# Battery_Manager.net
KiCad netlist of a schematic drawn in Altium Designer
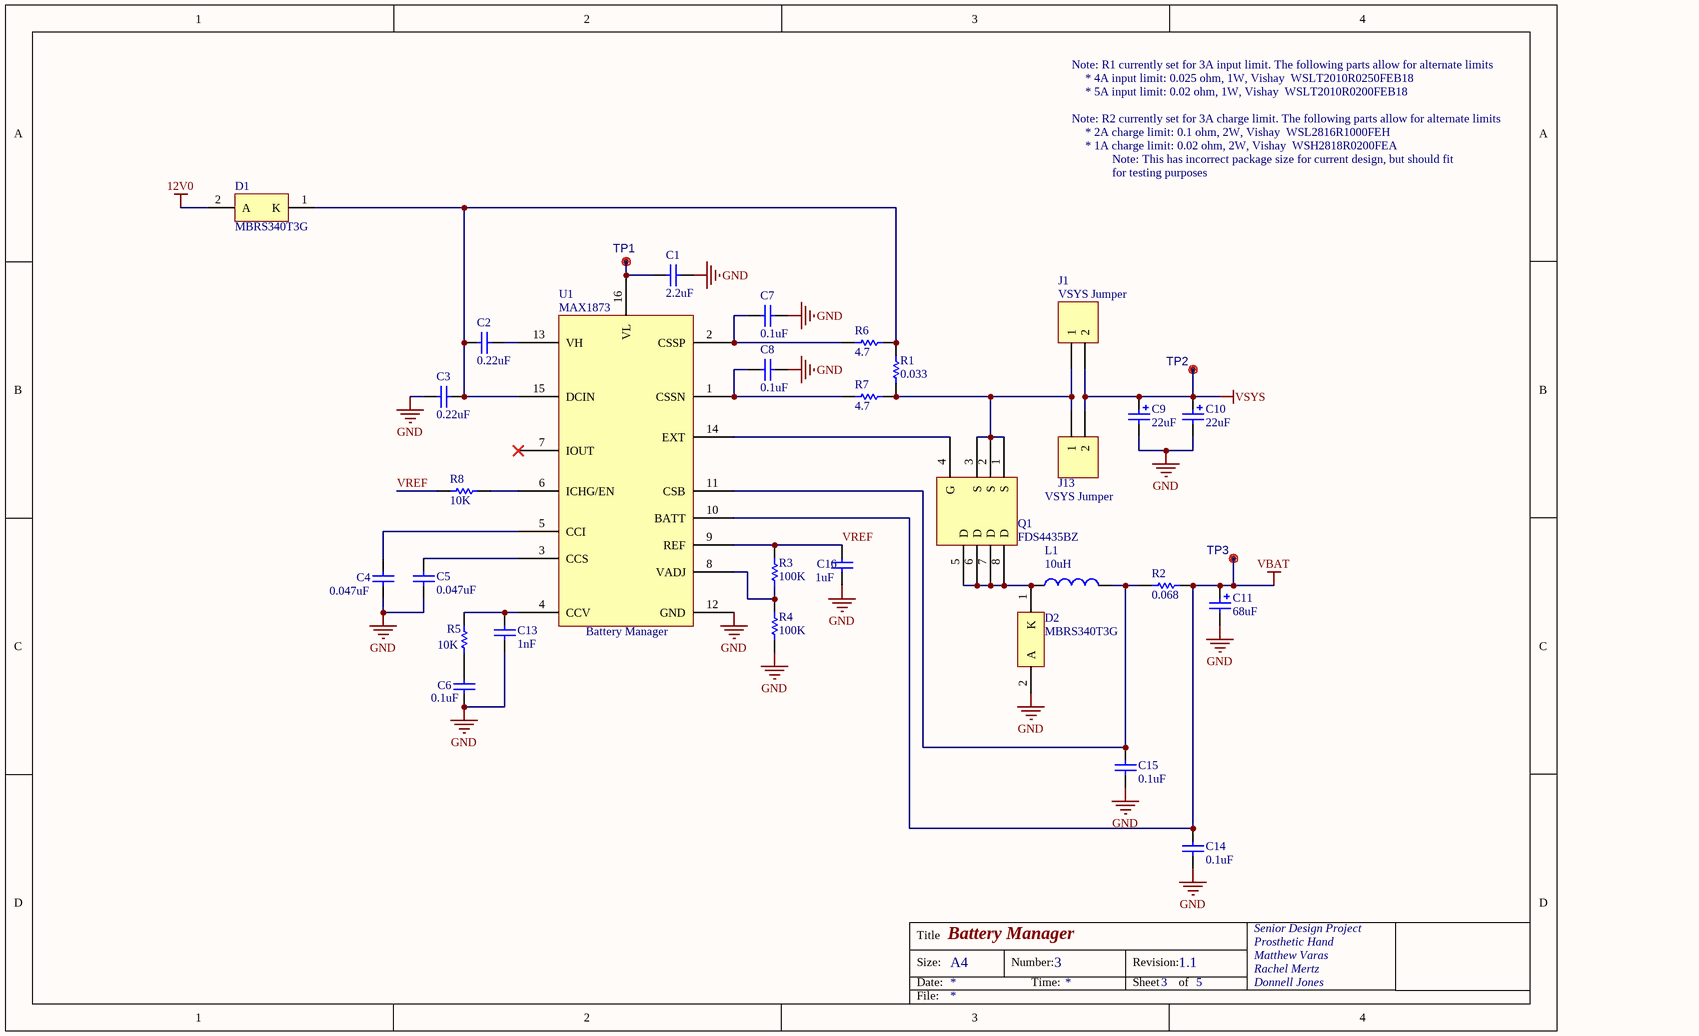
[diagram p0: Battery Manager.SchDoc]

(export (version "E")
  (design (tool "Eeschema 10.0.6"))
  (components
    (comp (ref "C1")
      (value "2.2uF")
      (footprint "CAPC0805(2012)145_N")
      (description "CAP CER 2.2UF 50V X5R 0805")
      (fields (field (name "TOLERANCE") "Â±10%"))
      (libsource (lib "Altium Content Vault") (part "CMP-1036-04844-1"))
    )
    (comp (ref "C2")
      (value "0.22uF")
      (footprint "CAPC0805(2012)145_N")
      (description "CAP CER 0.22UF 35V X5R 0805")
      (fields (field (name "TOLERANCE") "Â±10%"))
      (libsource (lib "Altium Content Vault") (part "CMP-1036-04552-1"))
    )
    (comp (ref "C3")
      (value "0.22uF")
      (footprint "CAPC0805(2012)145_N")
      (description "CAP CER 0.22UF 35V X5R 0805")
      (fields (field (name "TOLERANCE") "Â±10%"))
      (libsource (lib "Altium Content Vault") (part "CMP-1036-04552-1"))
    )
    (comp (ref "C4")
      (value "0.047uF")
      (footprint "CAPC0805(2012)75_N")
      (description "CAP CER 0.047UF 50V X7R 0805")
      (fields (field (name "TOLERANCE") "Â±10%"))
      (libsource (lib "Altium Content Vault") (part "CMP-1036-04259-1"))
    )
    (comp (ref "C5")
      (value "0.047uF")
      (footprint "CAPC0805(2012)75_N")
      (description "CAP CER 0.047UF 50V X7R 0805")
      (fields (field (name "TOLERANCE") "Â±10%"))
      (libsource (lib "Altium Content Vault") (part "CMP-1036-04259-1"))
    )
    (comp (ref "C6")
      (value "0.1uF")
      (footprint "CAPC0805(2012)145_N")
      (description "CAP CER 0.1UF 50V X7R 0805")
      (fields (field (name "TOLERANCE") "Â±10%"))
      (libsource (lib "Altium Content Vault") (part "CMP-1036-04419-1"))
    )
    (comp (ref "C7")
      (value "0.1uF")
      (footprint "CAPC0805(2012)145_N")
      (description "CAP CER 0.1UF 50V X7R 0805")
      (fields (field (name "TOLERANCE") "Â±10%"))
      (libsource (lib "Altium Content Vault") (part "CMP-1036-04419-1"))
    )
    (comp (ref "C8")
      (value "0.1uF")
      (footprint "CAPC0805(2012)145_N")
      (description "CAP CER 0.1UF 50V X7R 0805")
      (fields (field (name "TOLERANCE") "Â±10%"))
      (libsource (lib "Altium Content Vault") (part "CMP-1036-04419-1"))
    )
    (comp (ref "C9")
      (value "22uF")
      (footprint "Cap Tant D")
      (description "CAP TANT 22UF 35V 10% 2917")
      (libsource (lib "Miscellaneous Devices") (part "Cap Pol2"))
    )
    (comp (ref "C10")
      (value "22uF")
      (footprint "Cap Tant D")
      (description "CAP TANT 22UF 35V 10% 2917")
      (libsource (lib "Miscellaneous Devices") (part "Cap Pol2"))
    )
    (comp (ref "C11")
      (value "68uF")
      (footprint "Cap Tant E")
      (description "CAP TANT 68UF 25V 20% 2917")
      (libsource (lib "Miscellaneous Devices") (part "Cap Pol2"))
    )
    (comp (ref "C13")
      (value "1nF")
      (footprint "CAPC0603(1608)100_N")
      (description "CAP CER 1000PF 50V X7R 0603")
      (fields (field (name "TOLERANCE") "Â±10%"))
      (libsource (lib "Altium Content Vault") (part "CMP-1035-01889-1"))
    )
    (comp (ref "C14")
      (value "0.1uF")
      (footprint "CAPC0805(2012)145_N")
      (description "CAP CER 0.1UF 50V X7R 0805")
      (fields (field (name "TOLERANCE") "Â±10%"))
      (libsource (lib "Altium Content Vault") (part "CMP-1036-04419-1"))
    )
    (comp (ref "C15")
      (value "0.1uF")
      (footprint "CAPC0805(2012)145_N")
      (description "CAP CER 0.1UF 50V X7R 0805")
      (fields (field (name "TOLERANCE") "Â±10%"))
      (libsource (lib "Altium Content Vault") (part "CMP-1036-04419-1"))
    )
    (comp (ref "C16")
      (value "1uF")
      (footprint "CAPC0805(2012)100_N")
      (description "CAP CER 1UF 25V X7R 0805")
      (fields (field (name "TOLERANCE") "Â±10%"))
      (libsource (lib "Altium Content Vault") (part "CMP-1036-04737-1"))
    )
    (comp (ref "D1")
      (value "MBRS340T3G")
      (footprint "ONSC-SMC-2-403-03_V")
      (description "DIODE SCHOTTKY 40V 4A SMC")
      (fields (field (name "MANUFACTURER") "On Semiconductor"))
      (libsource (lib "") (part "CMP-1055-00380-1_1"))
    )
    (comp (ref "D2")
      (value "MBRS340T3G")
      (footprint "ONSC-SMC-2-403-03_V")
      (description "DIODE SCHOTTKY 40V 4A SMC")
      (fields (field (name "MANUFACTURER") "On Semiconductor"))
      (libsource (lib "Altium Content Vault") (part "CMP-1055-00380-1"))
    )
    (comp (ref "J1")
      (value "VSYS Jumper")
      (footprint "HDR1X2")
      (description "CONN HEADER .100 SINGL STR 2POS")
      (fields (field (name "PUBLISHER") "Altium Limited"))
      (libsource (lib "Miscellaneous Connectors") (part "Header 2"))
    )
    (comp (ref "J13")
      (value "VSYS Jumper")
      (footprint "HDR1X2")
      (description "CONN HEADER .100 SINGL STR 2POS")
      (fields (field (name "PUBLISHER") "Altium Limited"))
      (libsource (lib "") (part "Header 2_1"))
    )
    (comp (ref "L1")
      (value "10uH")
      (footprint "SRR1260 Ind")
      (description "FIXED IND 10UH 5.5A 20 MOHM SMD")
      (libsource (lib "Prosthetic Hand Schematic Lib") (part "SRR1260A-100MCT-ND"))
    )
    (comp (ref "Q1")
      (value "FDS4435BZ")
      (footprint "SOIC-8")
      (description "MOSFET P-CH 30V 8.8A 8-SOIC")
      (libsource (lib "Prosthetic Hand Schematic Lib") (part "FDS4435BZ"))
    )
    (comp (ref "R1")
      (value "0.033")
      (footprint "RESC2010(5025)_N")
      (description "RES SMD 0.033 OHM 1% 1W 2010")
      (fields (field (name "TOLERANCE") "1%") (field (name "POWER") "1W"))
      (libsource (lib "Altium Content Vault") (part "CMP-1017-00002-1"))
    )
    (comp (ref "R2")
      (value "0.068")
      (footprint "WSL2816")
      (description "RES SMD 0.068 OHM 1% 2W 2816")
      (fields (field (name "TOLERANCE") "1%") (field (name "POWER") "2W"))
      (libsource (lib "altium-import") (part "root_2_CMP-1017-00002-1_"))
    )
    (comp (ref "R3")
      (value "100K")
      (footprint "RESC0805(2012)_N")
      (description "RES SMD 100K OHM 1% 1/8W 0805")
      (fields (field (name "TOLERANCE") "1 %") (field (name "POWER") "0.125 W"))
      (libsource (lib "Altium Content Vault") (part "CMP-1013-00736-1"))
    )
    (comp (ref "R4")
      (value "100K")
      (footprint "RESC0805(2012)_N")
      (description "RES SMD 100K OHM 1% 1/8W 0805")
      (fields (field (name "TOLERANCE") "1 %") (field (name "POWER") "0.125 W"))
      (libsource (lib "Altium Content Vault") (part "CMP-1013-00736-1"))
    )
    (comp (ref "R5")
      (value "10K")
      (footprint "RESC0805(2012)_N")
      (description "RES SMD 10K OHM 1% 1/8W 0805")
      (fields (field (name "TOLERANCE") "1 %") (field (name "POWER") "0.125 W"))
      (libsource (lib "Altium Content Vault") (part "CMP-1013-00623-1"))
    )
    (comp (ref "R6")
      (value "4.7")
      (footprint "RESC0603(1608)_N")
      (description "RES SMD 4.7 OHM 1% 1/10W 0603")
      (fields (field (name "POWER") "0.1 W") (field (name "TOLERANCE") "1 %"))
      (libsource (lib "Altium Content Vault") (part "CMP-1012-00247-1"))
    )
    (comp (ref "R7")
      (value "4.7")
      (footprint "RESC0603(1608)_N")
      (description "RES SMD 4.7 OHM 1% 1/10W 0603")
      (fields (field (name "POWER") "0.1 W") (field (name "TOLERANCE") "1 %"))
      (libsource (lib "Altium Content Vault") (part "CMP-1012-00247-1"))
    )
    (comp (ref "R8")
      (value "10K")
      (footprint "RESC0805(2012)_N")
      (description "RES SMD 10K OHM 1% 1/8W 0805")
      (fields (field (name "TOLERANCE") "1 %") (field (name "POWER") "0.125 W"))
      (libsource (lib "Altium Content Vault") (part "CMP-1013-00623-1"))
    )
    (comp (ref "TP1")
      (value "Test Point")
      (footprint "Testpoint_70")
      (description "Test Pad")
      (libsource (lib "Prosthetic Hand Schematic Lib") (part "Test Point"))
    )
    (comp (ref "TP2")
      (value "Test Point")
      (footprint "Testpoint_70")
      (description "Test Pad")
      (libsource (lib "Prosthetic Hand Schematic Lib") (part "Test Point"))
    )
    (comp (ref "TP3")
      (value "Test Point")
      (footprint "Testpoint_70")
      (description "Test Pad")
      (libsource (lib "Prosthetic Hand Schematic Lib") (part "Test Point"))
    )
    (comp (ref "U1")
      (value "MAX1873")
      (footprint "QSOP-16")
      (description "IC CNTRLR CHARGE LI+ 16-QSOP")
      (fields (field (name "DESC") "Battery Manager"))
      (libsource (lib "Prosthetic Hand Schematic Lib") (part "MAX1873"))
    )
  )
  (nets
    (net (code "1") (name "/VREF") (class "Default")
      (node (ref "C16") (pin "2") (pinfunction "2_2") (pintype "passive"))
      (node (ref "R3") (pin "2") (pinfunction "2_2") (pintype "passive"))
      (node (ref "R8") (pin "2") (pinfunction "2_2") (pintype "passive"))
      (node (ref "U1") (pin "9") (pinfunction "REF_9") (pintype "passive"))
    )
    (net (code "2") (name "12V0") (class "Default")
      (node (ref "D1") (pin "2") (pinfunction "A_2") (pintype "passive"))
    )
    (net (code "3") (name "GND") (class "Default")
      (node (ref "C1") (pin "2") (pinfunction "2_2") (pintype "passive"))
      (node (ref "C10") (pin "2") (pinfunction "2_2") (pintype "passive"))
      (node (ref "C11") (pin "2") (pinfunction "2_2") (pintype "passive"))
      (node (ref "C13") (pin "1") (pinfunction "1_1") (pintype "passive"))
      (node (ref "C14") (pin "2") (pinfunction "2_2") (pintype "passive"))
      (node (ref "C15") (pin "1") (pinfunction "1_1") (pintype "passive"))
      (node (ref "C16") (pin "1") (pinfunction "1_1") (pintype "passive"))
      (node (ref "C3") (pin "2") (pinfunction "2_2") (pintype "passive"))
      (node (ref "C4") (pin "2") (pinfunction "2_2") (pintype "passive"))
      (node (ref "C5") (pin "2") (pinfunction "2_2") (pintype "passive"))
      (node (ref "C6") (pin "1") (pinfunction "1_1") (pintype "passive"))
      (node (ref "C7") (pin "1") (pinfunction "1_1") (pintype "passive"))
      (node (ref "C8") (pin "1") (pinfunction "1_1") (pintype "passive"))
      (node (ref "C9") (pin "2") (pinfunction "2_2") (pintype "passive"))
      (node (ref "D2") (pin "2") (pinfunction "A_2") (pintype "passive"))
      (node (ref "R4") (pin "1") (pinfunction "1_1") (pintype "passive"))
      (node (ref "U1") (pin "12") (pinfunction "GND_12") (pintype "passive"))
    )
    (net (code "4") (name "Net-(C6-Pad2)") (class "Default")
      (node (ref "C6") (pin "2") (pinfunction "2_2") (pintype "passive"))
      (node (ref "R5") (pin "2") (pinfunction "2_2") (pintype "passive"))
    )
    (net (code "5") (name "Net-(D1-K)") (class "Default")
      (node (ref "C2") (pin "1") (pinfunction "1_1") (pintype "passive"))
      (node (ref "C3") (pin "1") (pinfunction "1_1") (pintype "passive"))
      (node (ref "D1") (pin "1") (pinfunction "K_1") (pintype "passive"))
      (node (ref "R1") (pin "2") (pinfunction "2_2") (pintype "passive"))
      (node (ref "R6") (pin "1") (pinfunction "1_1") (pintype "passive"))
      (node (ref "U1") (pin "15") (pinfunction "DCIN_15") (pintype "passive"))
    )
    (net (code "6") (name "Net-(D2-K)") (class "Default")
      (node (ref "D2") (pin "1") (pinfunction "K_1") (pintype "passive"))
      (node (ref "L1") (pin "1") (pinfunction "1_1") (pintype "passive"))
      (node (ref "Q1") (pin "5") (pinfunction "D_5") (pintype "passive"))
      (node (ref "Q1") (pin "6") (pinfunction "D_6") (pintype "passive"))
      (node (ref "Q1") (pin "7") (pinfunction "D_7") (pintype "passive"))
      (node (ref "Q1") (pin "8") (pinfunction "D_8") (pintype "passive"))
    )
    (net (code "7") (name "Net-(J1-Pad1)") (class "Default")
      (node (ref "J1") (pin "1") (pinfunction "1_1") (pintype "passive"))
      (node (ref "J13") (pin "1") (pinfunction "1_1") (pintype "passive"))
      (node (ref "Q1") (pin "1") (pinfunction "S_1") (pintype "passive"))
      (node (ref "Q1") (pin "2") (pinfunction "S_2") (pintype "passive"))
      (node (ref "Q1") (pin "3") (pinfunction "S_3") (pintype "passive"))
      (node (ref "R1") (pin "1") (pinfunction "1_1") (pintype "passive"))
      (node (ref "R7") (pin "1") (pinfunction "1_1") (pintype "passive"))
    )
    (net (code "8") (name "Net-(Q1-G)") (class "Default")
      (node (ref "Q1") (pin "4") (pinfunction "G_4") (pintype "passive"))
      (node (ref "U1") (pin "14") (pinfunction "EXT_14") (pintype "passive"))
    )
    (net (code "9") (name "Net-(TP1-M80)") (class "Default")
      (node (ref "C1") (pin "1") (pinfunction "1_1") (pintype "passive"))
      (node (ref "TP1") (pin "1") (pinfunction "M80_1") (pintype "passive"))
      (node (ref "U1") (pin "16") (pinfunction "VL_16") (pintype "passive"))
    )
    (net (code "10") (name "Net-(U1-CCI)") (class "Default")
      (node (ref "C4") (pin "1") (pinfunction "1_1") (pintype "passive"))
      (node (ref "U1") (pin "5") (pinfunction "CCI_5") (pintype "passive"))
    )
    (net (code "11") (name "Net-(U1-CCS)") (class "Default")
      (node (ref "C5") (pin "1") (pinfunction "1_1") (pintype "passive"))
      (node (ref "U1") (pin "3") (pinfunction "CCS_3") (pintype "passive"))
    )
    (net (code "12") (name "Net-(U1-CCV)") (class "Default")
      (node (ref "C13") (pin "2") (pinfunction "2_2") (pintype "passive"))
      (node (ref "R5") (pin "1") (pinfunction "1_1") (pintype "passive"))
      (node (ref "U1") (pin "4") (pinfunction "CCV_4") (pintype "passive"))
    )
    (net (code "13") (name "Net-(U1-CSB)") (class "Default")
      (node (ref "C15") (pin "2") (pinfunction "2_2") (pintype "passive"))
      (node (ref "L1") (pin "2") (pinfunction "2_2") (pintype "passive"))
      (node (ref "R2") (pin "2") (pinfunction "2_2") (pintype "passive"))
      (node (ref "U1") (pin "11") (pinfunction "CSB_11") (pintype "passive"))
    )
    (net (code "14") (name "Net-(U1-CSSN)") (class "Default")
      (node (ref "C8") (pin "2") (pinfunction "2_2") (pintype "passive"))
      (node (ref "R7") (pin "2") (pinfunction "2_2") (pintype "passive"))
      (node (ref "U1") (pin "1") (pinfunction "CSSN_1") (pintype "passive"))
    )
    (net (code "15") (name "Net-(U1-CSSP)") (class "Default")
      (node (ref "C7") (pin "2") (pinfunction "2_2") (pintype "passive"))
      (node (ref "R6") (pin "2") (pinfunction "2_2") (pintype "passive"))
      (node (ref "U1") (pin "2") (pinfunction "CSSP_2") (pintype "passive"))
    )
    (net (code "16") (name "Net-(U1-ICHG{slash}EN)") (class "Default")
      (node (ref "R8") (pin "1") (pinfunction "1_1") (pintype "passive"))
      (node (ref "U1") (pin "6") (pinfunction "ICHG/EN_6") (pintype "passive"))
    )
    (net (code "17") (name "Net-(U1-VADJ)") (class "Default")
      (node (ref "R3") (pin "1") (pinfunction "1_1") (pintype "passive"))
      (node (ref "R4") (pin "2") (pinfunction "2_2") (pintype "passive"))
      (node (ref "U1") (pin "8") (pinfunction "VADJ_8") (pintype "passive"))
    )
    (net (code "18") (name "Net-(U1-VH)") (class "Default")
      (node (ref "C2") (pin "2") (pinfunction "2_2") (pintype "passive"))
      (node (ref "U1") (pin "13") (pinfunction "VH_13") (pintype "passive"))
    )
    (net (code "19") (name "VBAT") (class "Default")
      (node (ref "C11") (pin "1") (pinfunction "1_1") (pintype "passive"))
      (node (ref "C14") (pin "1") (pinfunction "1_1") (pintype "passive"))
      (node (ref "R2") (pin "1") (pinfunction "1_1") (pintype "passive"))
      (node (ref "TP3") (pin "1") (pinfunction "M80_1") (pintype "passive"))
      (node (ref "U1") (pin "10") (pinfunction "BATT_10") (pintype "passive"))
    )
    (net (code "20") (name "VSYS") (class "Default")
      (node (ref "C10") (pin "1") (pinfunction "1_1") (pintype "passive"))
      (node (ref "C9") (pin "1") (pinfunction "1_1") (pintype "passive"))
      (node (ref "J1") (pin "2") (pinfunction "2_2") (pintype "passive"))
      (node (ref "J13") (pin "2") (pinfunction "2_2") (pintype "passive"))
      (node (ref "TP2") (pin "1") (pinfunction "M80_1") (pintype "passive"))
    )
    (net (code "21") (name "unconnected-(U1-IOUT-Pad7)") (class "Default")
      (node (ref "U1") (pin "7") (pinfunction "IOUT_7") (pintype "passive+no_connect"))
    )
  )
)
